# Controller_Section.net
KiCad netlist of a schematic drawn in Altium Designer
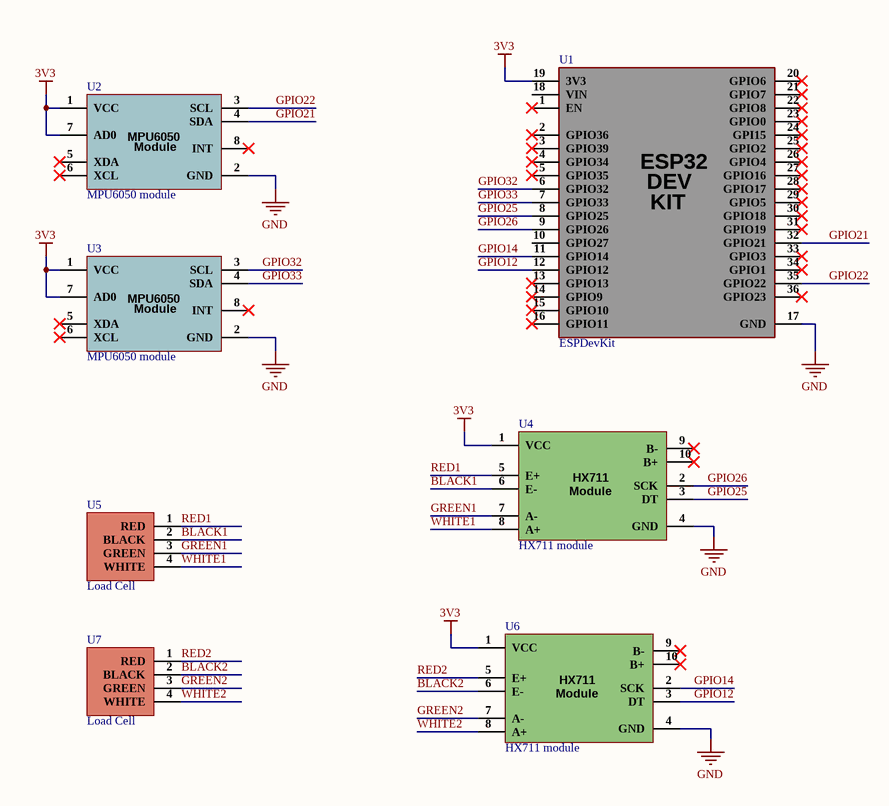
[diagram p0: Controller Section.SchDoc]

(export (version "E")
  (design (tool "Eeschema 10.0.6"))
  (components
    (comp (ref "U1") (value "ESPDevKit") (libsource (lib "SS_Int_Lib") (part "ESP Dev Kit")))
    (comp (ref "U2") (value "MPU6050 module") (libsource (lib "SS_Int_Lib") (part "MPU6050 module")))
    (comp (ref "U3") (value "MPU6050 module") (libsource (lib "SS_Int_Lib") (part "MPU6050 module")))
    (comp (ref "U4") (value "HX711 module") (libsource (lib "SS_Int_Lib") (part "HX711 module")))
    (comp (ref "U5") (value "Load Cell") (libsource (lib "SS_Int_Lib") (part "Load cell")))
    (comp (ref "U6") (value "HX711 module") (libsource (lib "SS_Int_Lib") (part "HX711 module")))
    (comp (ref "U7") (value "Load Cell") (libsource (lib "SS_Int_Lib") (part "Load cell")))
  )
  (nets
    (net (code "1") (name "/BLACK1") (class "Default")
      (node (ref "U4") (pin "6") (pinfunction "E-_6") (pintype "passive"))
      (node (ref "U5") (pin "2") (pinfunction "BLACK_2") (pintype "passive"))
    )
    (net (code "2") (name "/BLACK2") (class "Default")
      (node (ref "U6") (pin "6") (pinfunction "E-_6") (pintype "passive"))
      (node (ref "U7") (pin "2") (pinfunction "BLACK_2") (pintype "passive"))
    )
    (net (code "3") (name "/GPIO12") (class "Default")
      (node (ref "U1") (pin "12") (pinfunction "GPIO12_12") (pintype "passive"))
      (node (ref "U6") (pin "3") (pinfunction "DT_3") (pintype "passive"))
    )
    (net (code "4") (name "/GPIO14") (class "Default")
      (node (ref "U1") (pin "11") (pinfunction "GPIO14_11") (pintype "passive"))
      (node (ref "U6") (pin "2") (pinfunction "SCK_2") (pintype "passive"))
    )
    (net (code "5") (name "/GPIO21") (class "Default")
      (node (ref "U1") (pin "32") (pinfunction "GPIO21_32") (pintype "passive"))
      (node (ref "U2") (pin "4") (pinfunction "SDA_4") (pintype "passive"))
    )
    (net (code "6") (name "/GPIO22") (class "Default")
      (node (ref "U1") (pin "35") (pinfunction "GPIO22_35") (pintype "passive"))
      (node (ref "U2") (pin "3") (pinfunction "SCL_3") (pintype "passive"))
    )
    (net (code "7") (name "/GPIO25") (class "Default")
      (node (ref "U1") (pin "8") (pinfunction "GPIO25_8") (pintype "passive"))
      (node (ref "U4") (pin "3") (pinfunction "DT_3") (pintype "passive"))
    )
    (net (code "8") (name "/GPIO26") (class "Default")
      (node (ref "U1") (pin "9") (pinfunction "GPIO26_9") (pintype "passive"))
      (node (ref "U4") (pin "2") (pinfunction "SCK_2") (pintype "passive"))
    )
    (net (code "9") (name "/GPIO32") (class "Default")
      (node (ref "U1") (pin "6") (pinfunction "GPIO32_6") (pintype "passive"))
      (node (ref "U3") (pin "3") (pinfunction "SCL_3") (pintype "passive"))
    )
    (net (code "10") (name "/GPIO33") (class "Default")
      (node (ref "U1") (pin "7") (pinfunction "GPIO33_7") (pintype "passive"))
      (node (ref "U3") (pin "4") (pinfunction "SDA_4") (pintype "passive"))
    )
    (net (code "11") (name "/GREEN1") (class "Default")
      (node (ref "U4") (pin "7") (pinfunction "A-_7") (pintype "passive"))
      (node (ref "U5") (pin "3") (pinfunction "GREEN_3") (pintype "passive"))
    )
    (net (code "12") (name "/GREEN2") (class "Default")
      (node (ref "U6") (pin "7") (pinfunction "A-_7") (pintype "passive"))
      (node (ref "U7") (pin "3") (pinfunction "GREEN_3") (pintype "passive"))
    )
    (net (code "13") (name "/RED1") (class "Default")
      (node (ref "U4") (pin "5") (pinfunction "E+_5") (pintype "passive"))
      (node (ref "U5") (pin "1") (pinfunction "RED_1") (pintype "passive"))
    )
    (net (code "14") (name "/RED2") (class "Default")
      (node (ref "U6") (pin "5") (pinfunction "E+_5") (pintype "passive"))
      (node (ref "U7") (pin "1") (pinfunction "RED_1") (pintype "passive"))
    )
    (net (code "15") (name "/WHITE1") (class "Default")
      (node (ref "U4") (pin "8") (pinfunction "A+_8") (pintype "passive"))
      (node (ref "U5") (pin "4") (pinfunction "WHITE_4") (pintype "passive"))
    )
    (net (code "16") (name "/WHITE2") (class "Default")
      (node (ref "U6") (pin "8") (pinfunction "A+_8") (pintype "passive"))
      (node (ref "U7") (pin "4") (pinfunction "WHITE_4") (pintype "passive"))
    )
    (net (code "17") (name "3V3") (class "Default")
      (node (ref "U1") (pin "19") (pinfunction "3V3_19") (pintype "passive"))
      (node (ref "U2") (pin "1") (pinfunction "VCC_1") (pintype "passive"))
      (node (ref "U2") (pin "7") (pinfunction "AD0_7") (pintype "passive"))
      (node (ref "U3") (pin "1") (pinfunction "VCC_1") (pintype "passive"))
      (node (ref "U3") (pin "7") (pinfunction "AD0_7") (pintype "passive"))
      (node (ref "U4") (pin "1") (pinfunction "VCC_1") (pintype "passive"))
      (node (ref "U6") (pin "1") (pinfunction "VCC_1") (pintype "passive"))
    )
    (net (code "18") (name "GND") (class "Default")
      (node (ref "U1") (pin "17") (pinfunction "GND_17") (pintype "passive"))
      (node (ref "U2") (pin "2") (pinfunction "GND_2") (pintype "passive"))
      (node (ref "U3") (pin "2") (pinfunction "GND_2") (pintype "passive"))
      (node (ref "U4") (pin "4") (pinfunction "GND_4") (pintype "passive"))
      (node (ref "U6") (pin "4") (pinfunction "GND_4") (pintype "passive"))
    )
    (net (code "19") (name "unconnected-(U1-EN-Pad1)") (class "Default")
      (node (ref "U1") (pin "1") (pinfunction "EN_1") (pintype "passive+no_connect"))
    )
    (net (code "20") (name "unconnected-(U1-GPI15-Pad24)") (class "Default")
      (node (ref "U1") (pin "24") (pinfunction "GPI15_24") (pintype "passive+no_connect"))
    )
    (net (code "21") (name "unconnected-(U1-GPIO0-Pad23)") (class "Default")
      (node (ref "U1") (pin "23") (pinfunction "GPIO0_23") (pintype "passive+no_connect"))
    )
    (net (code "22") (name "unconnected-(U1-GPIO1-Pad34)") (class "Default")
      (node (ref "U1") (pin "34") (pinfunction "GPIO1_34") (pintype "passive+no_connect"))
    )
    (net (code "23") (name "unconnected-(U1-GPIO2-Pad25)") (class "Default")
      (node (ref "U1") (pin "25") (pinfunction "GPIO2_25") (pintype "passive+no_connect"))
    )
    (net (code "24") (name "unconnected-(U1-GPIO3-Pad33)") (class "Default")
      (node (ref "U1") (pin "33") (pinfunction "GPIO3_33") (pintype "passive+no_connect"))
    )
    (net (code "25") (name "unconnected-(U1-GPIO4-Pad26)") (class "Default")
      (node (ref "U1") (pin "26") (pinfunction "GPIO4_26") (pintype "passive+no_connect"))
    )
    (net (code "26") (name "unconnected-(U1-GPIO5-Pad29)") (class "Default")
      (node (ref "U1") (pin "29") (pinfunction "GPIO5_29") (pintype "passive+no_connect"))
    )
    (net (code "27") (name "unconnected-(U1-GPIO6-Pad20)") (class "Default")
      (node (ref "U1") (pin "20") (pinfunction "GPIO6_20") (pintype "passive+no_connect"))
    )
    (net (code "28") (name "unconnected-(U1-GPIO7-Pad21)") (class "Default")
      (node (ref "U1") (pin "21") (pinfunction "GPIO7_21") (pintype "passive+no_connect"))
    )
    (net (code "29") (name "unconnected-(U1-GPIO8-Pad22)") (class "Default")
      (node (ref "U1") (pin "22") (pinfunction "GPIO8_22") (pintype "passive+no_connect"))
    )
    (net (code "30") (name "unconnected-(U1-GPIO9-Pad14)") (class "Default")
      (node (ref "U1") (pin "14") (pinfunction "GPIO9_14") (pintype "passive+no_connect"))
    )
    (net (code "31") (name "unconnected-(U1-GPIO10-Pad15)") (class "Default")
      (node (ref "U1") (pin "15") (pinfunction "GPIO10_15") (pintype "passive+no_connect"))
    )
    (net (code "32") (name "unconnected-(U1-GPIO11-Pad16)") (class "Default")
      (node (ref "U1") (pin "16") (pinfunction "GPIO11_16") (pintype "passive+no_connect"))
    )
    (net (code "33") (name "unconnected-(U1-GPIO13-Pad13)") (class "Default")
      (node (ref "U1") (pin "13") (pinfunction "GPIO13_13") (pintype "passive+no_connect"))
    )
    (net (code "34") (name "unconnected-(U1-GPIO16-Pad27)") (class "Default")
      (node (ref "U1") (pin "27") (pinfunction "GPIO16_27") (pintype "passive+no_connect"))
    )
    (net (code "35") (name "unconnected-(U1-GPIO17-Pad28)") (class "Default")
      (node (ref "U1") (pin "28") (pinfunction "GPIO17_28") (pintype "passive+no_connect"))
    )
    (net (code "36") (name "unconnected-(U1-GPIO18-Pad30)") (class "Default")
      (node (ref "U1") (pin "30") (pinfunction "GPIO18_30") (pintype "passive+no_connect"))
    )
    (net (code "37") (name "unconnected-(U1-GPIO19-Pad31)") (class "Default")
      (node (ref "U1") (pin "31") (pinfunction "GPIO19_31") (pintype "passive+no_connect"))
    )
    (net (code "38") (name "unconnected-(U1-GPIO23-Pad36)") (class "Default")
      (node (ref "U1") (pin "36") (pinfunction "GPIO23_36") (pintype "passive+no_connect"))
    )
    (net (code "39") (name "unconnected-(U1-GPIO27-Pad10)") (class "Default")
      (node (ref "U1") (pin "10") (pinfunction "GPIO27_10") (pintype "passive"))
    )
    (net (code "40") (name "unconnected-(U1-GPIO34-Pad4)") (class "Default")
      (node (ref "U1") (pin "4") (pinfunction "GPIO34_4") (pintype "passive+no_connect"))
    )
    (net (code "41") (name "unconnected-(U1-GPIO35-Pad5)") (class "Default")
      (node (ref "U1") (pin "5") (pinfunction "GPIO35_5") (pintype "passive+no_connect"))
    )
    (net (code "42") (name "unconnected-(U1-GPIO36-Pad2)") (class "Default")
      (node (ref "U1") (pin "2") (pinfunction "GPIO36_2") (pintype "passive+no_connect"))
    )
    (net (code "43") (name "unconnected-(U1-GPIO39-Pad3)") (class "Default")
      (node (ref "U1") (pin "3") (pinfunction "GPIO39_3") (pintype "passive+no_connect"))
    )
    (net (code "44") (name "unconnected-(U1-VIN-Pad18)") (class "Default")
      (node (ref "U1") (pin "18") (pinfunction "VIN_18") (pintype "passive"))
    )
    (net (code "45") (name "unconnected-(U2-INT-Pad8)") (class "Default")
      (node (ref "U2") (pin "8") (pinfunction "INT_8") (pintype "passive+no_connect"))
    )
    (net (code "46") (name "unconnected-(U2-XCL-Pad6)") (class "Default")
      (node (ref "U2") (pin "6") (pinfunction "XCL_6") (pintype "passive+no_connect"))
    )
    (net (code "47") (name "unconnected-(U2-XDA-Pad5)") (class "Default")
      (node (ref "U2") (pin "5") (pinfunction "XDA_5") (pintype "passive+no_connect"))
    )
    (net (code "48") (name "unconnected-(U3-INT-Pad8)") (class "Default")
      (node (ref "U3") (pin "8") (pinfunction "INT_8") (pintype "passive+no_connect"))
    )
    (net (code "49") (name "unconnected-(U3-XCL-Pad6)") (class "Default")
      (node (ref "U3") (pin "6") (pinfunction "XCL_6") (pintype "passive+no_connect"))
    )
    (net (code "50") (name "unconnected-(U3-XDA-Pad5)") (class "Default")
      (node (ref "U3") (pin "5") (pinfunction "XDA_5") (pintype "passive+no_connect"))
    )
    (net (code "51") (name "unconnected-(U4-B+-Pad10)") (class "Default")
      (node (ref "U4") (pin "10") (pinfunction "B+_10") (pintype "passive+no_connect"))
    )
    (net (code "52") (name "unconnected-(U4-B--Pad9)") (class "Default")
      (node (ref "U4") (pin "9") (pinfunction "B-_9") (pintype "passive+no_connect"))
    )
    (net (code "53") (name "unconnected-(U6-B+-Pad10)") (class "Default")
      (node (ref "U6") (pin "10") (pinfunction "B+_10") (pintype "passive+no_connect"))
    )
    (net (code "54") (name "unconnected-(U6-B--Pad9)") (class "Default")
      (node (ref "U6") (pin "9") (pinfunction "B-_9") (pintype "passive+no_connect"))
    )
  )
)
